# hasp_interface.net
KiCad netlist of a schematic drawn in EAGLE
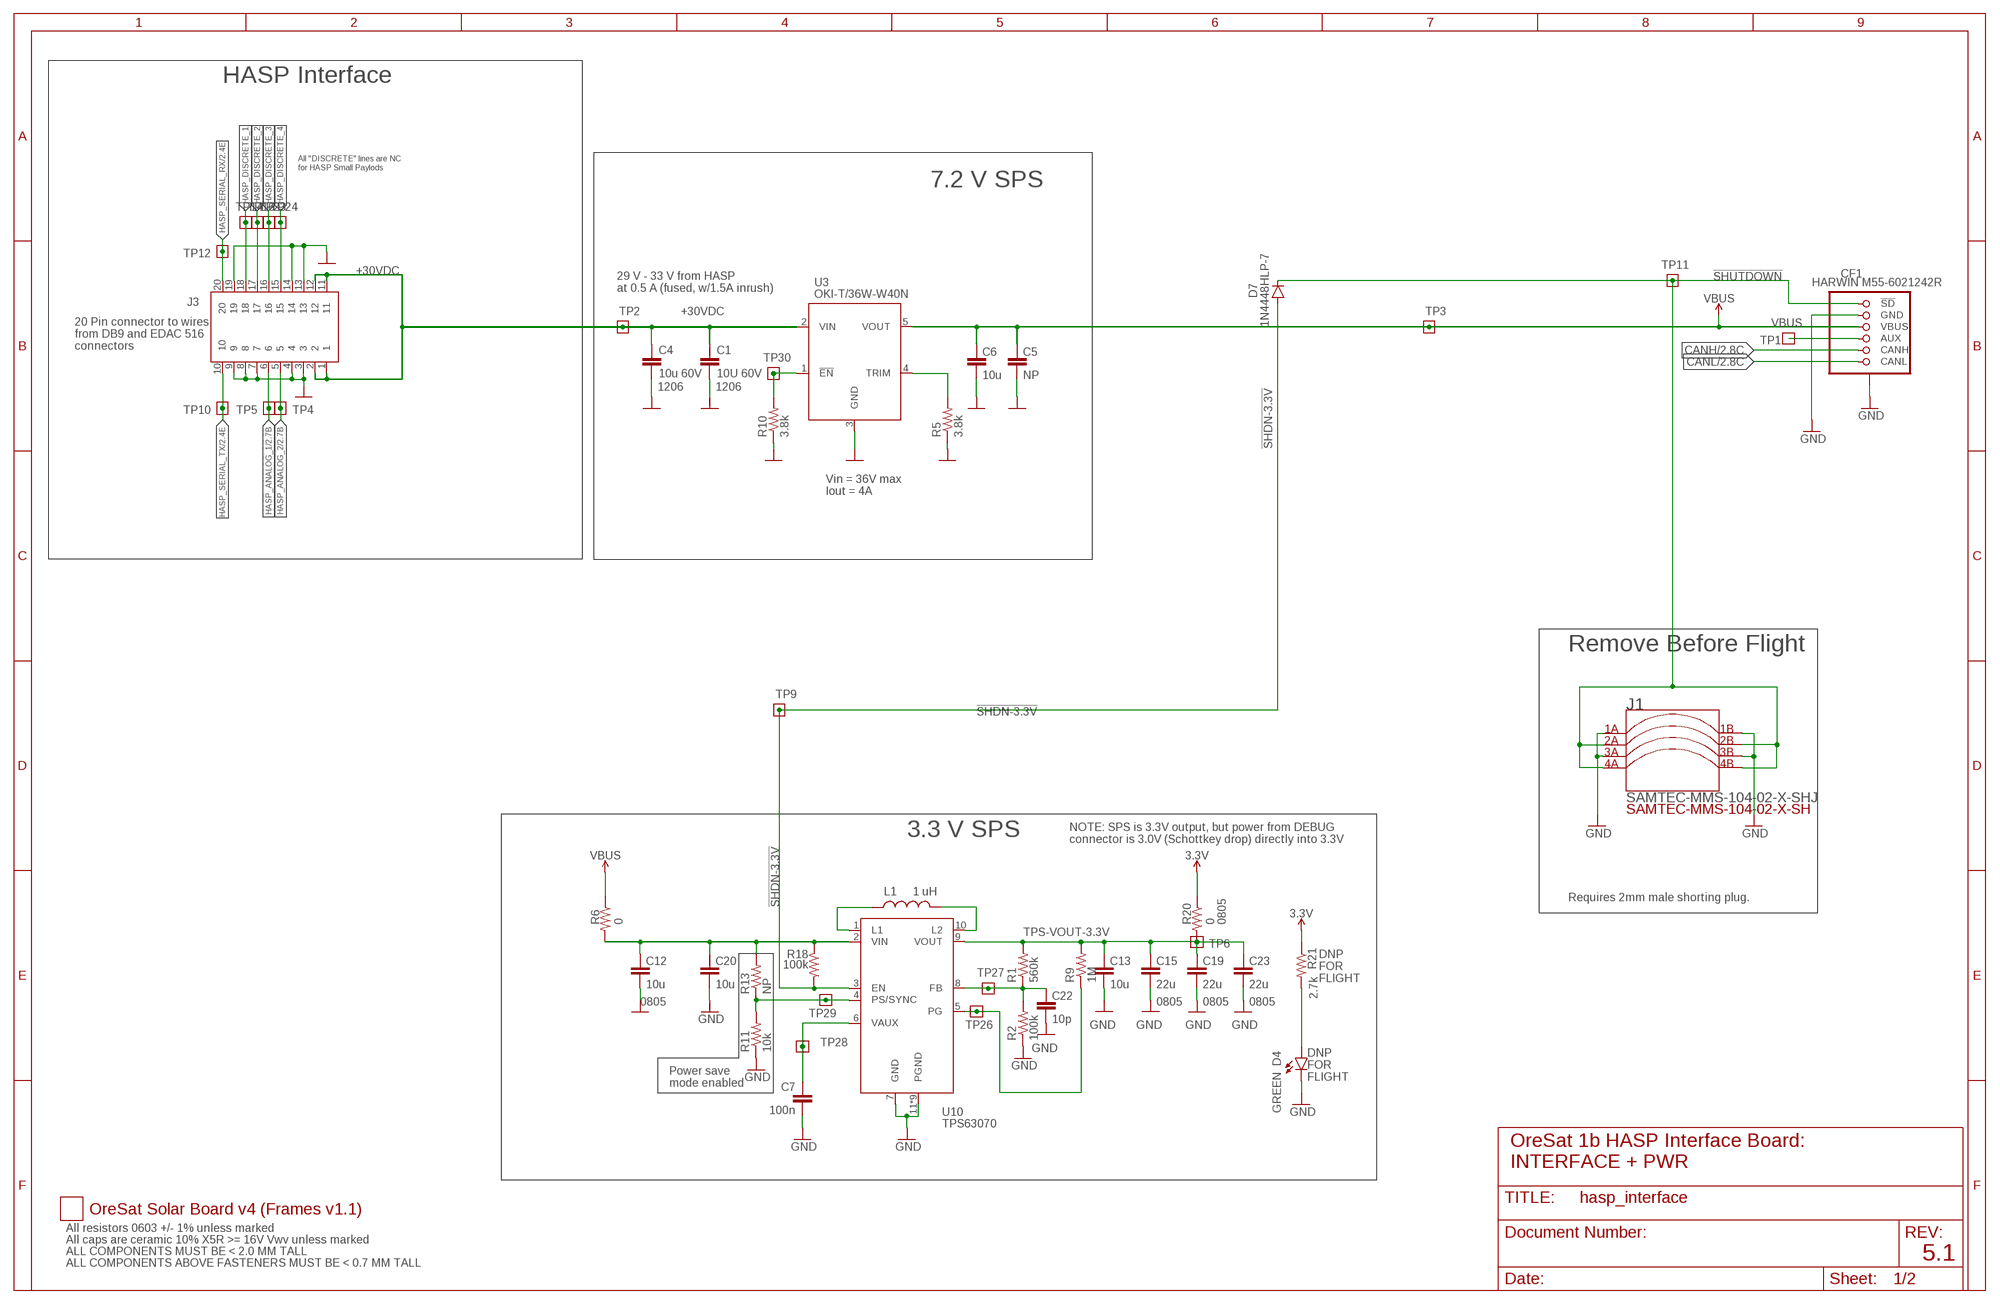
[diagram p0: schematic, sheet 1]
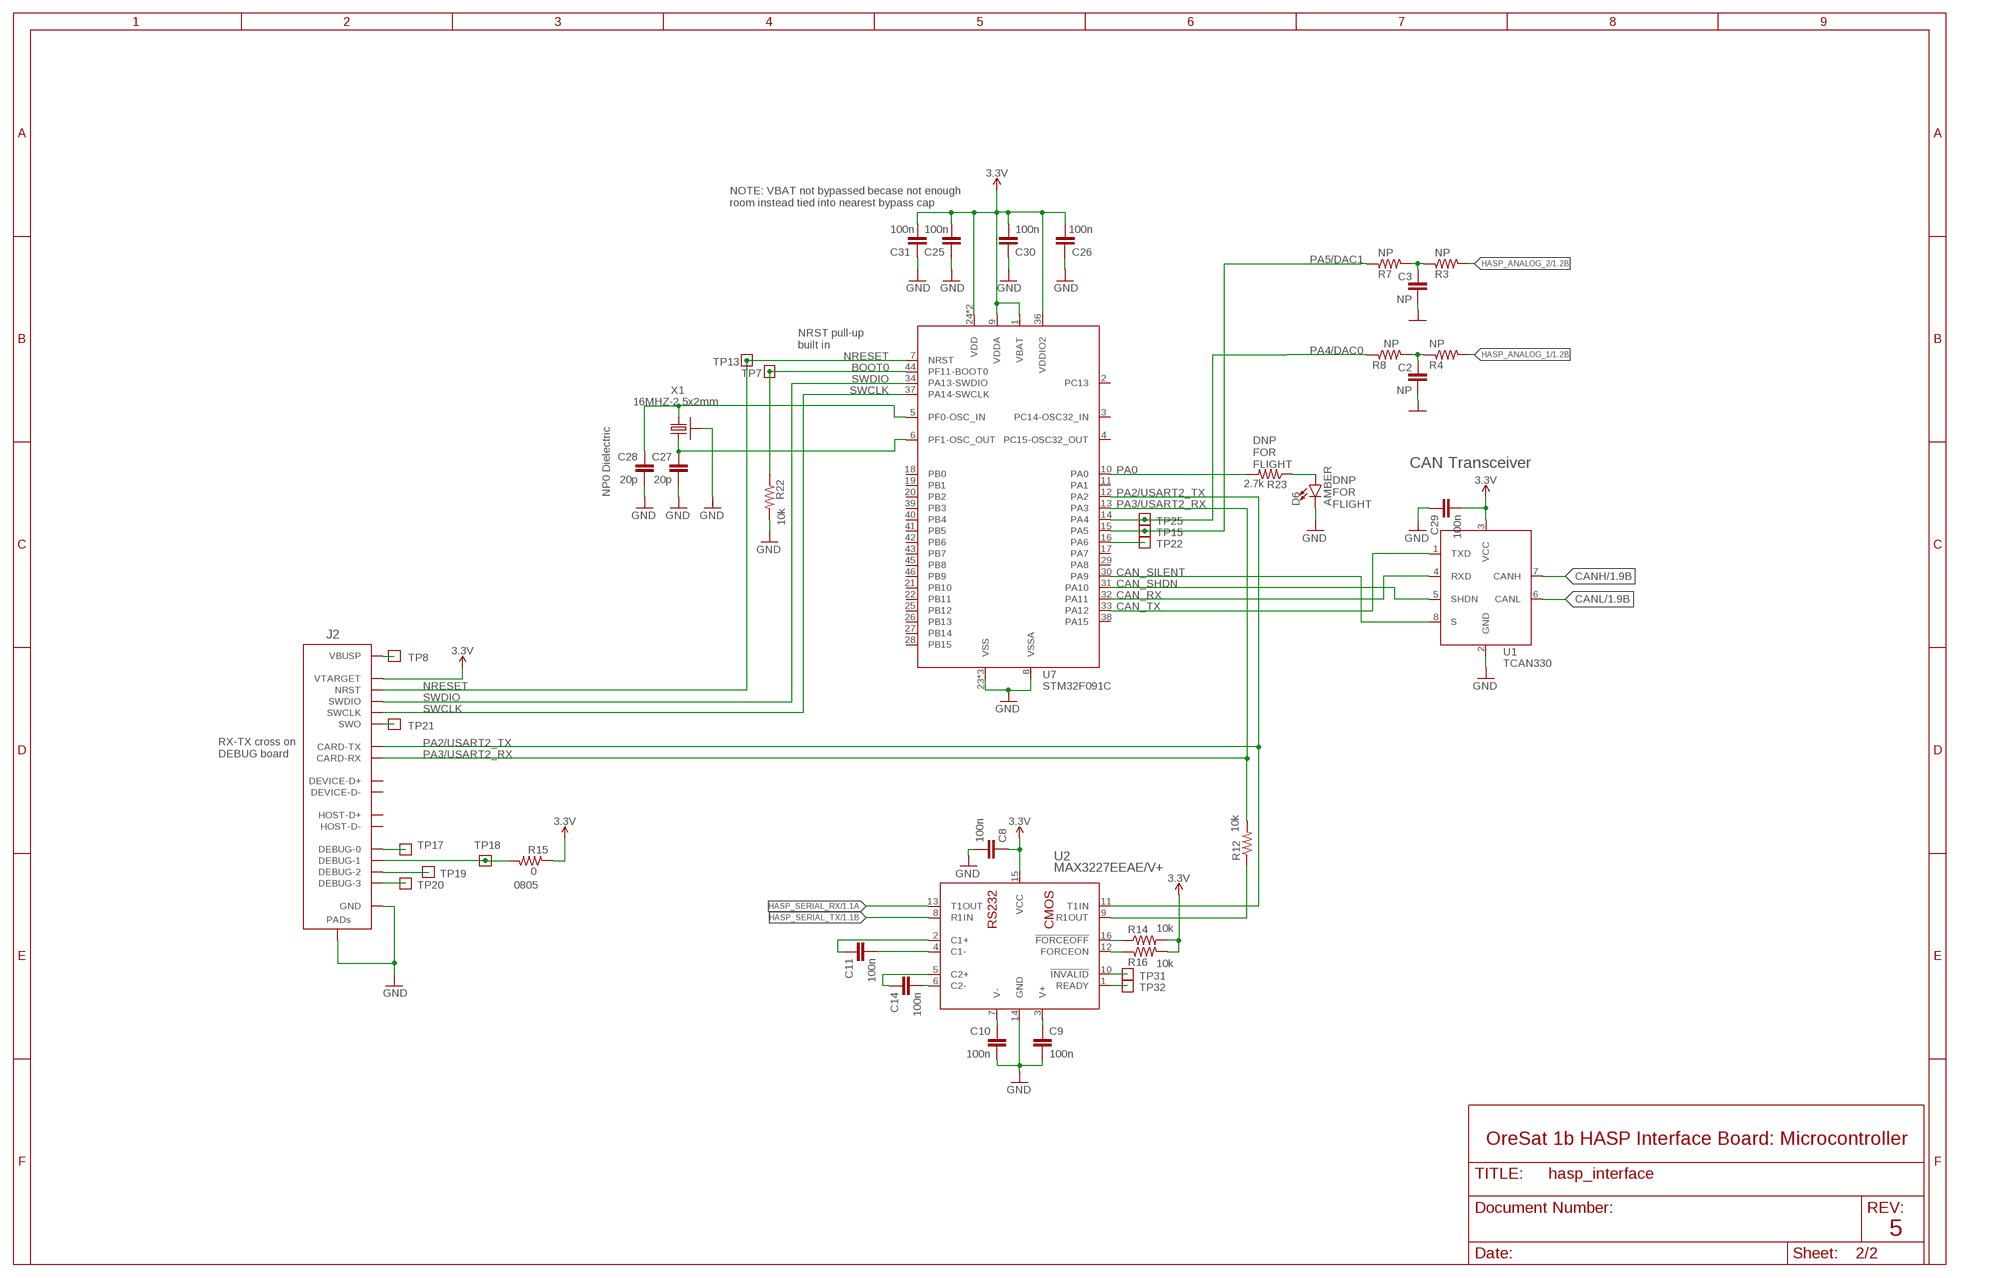
[diagram p1: schematic, sheet 2]

(export (version "E")
  (design (tool "Eeschema 10.0.6"))
  (components
    (comp (ref "C1")
      (value "10U 60V")
      (footprint "eagle-import:1206-C")
      (libsource (lib "eagle-import") (part "C-EU1206-C"))
    )
    (comp (ref "C4")
      (value "10u 60V")
      (footprint "eagle-import:1206-C")
      (libsource (lib "eagle-import") (part "C-EU1206-C"))
    )
    (comp (ref "C5")
      (value "NP")
      (footprint "eagle-import:.0603-C-NOSILK")
      (fields (field (name "MFR") "Murata") (field (name "MPN") "GRT188R61C106KE13D"))
      (libsource (lib "eagle-import") (part "C-EU0603-C-NOSILK"))
    )
    (comp (ref "C6")
      (value "10u")
      (footprint "eagle-import:.0603-C-NOSILK")
      (fields (field (name "MFR") "Murata") (field (name "MPN") "GRT188R61C106KE13D"))
      (libsource (lib "eagle-import") (part "C-EU0603-C-NOSILK"))
    )
    (comp (ref "C7")
      (value "100n")
      (footprint "eagle-import:.0603-C-NOSILK")
      (fields (field (name "MFR") "Kemet") (field (name "MPN") "CL10B104KB85PND"))
      (libsource (lib "eagle-import") (part "C-EU0603-C-NOSILK"))
    )
    (comp (ref "C12")
      (value "10u")
      (footprint "eagle-import:.0805-B-NOSILK")
      (fields (field (name "MFR") "Murata") (field (name "MPN") "GRT21BR61C106KE01L"))
      (libsource (lib "eagle-import") (part "C-EU0805-B-NOSILK"))
    )
    (comp (ref "C13")
      (value "10u")
      (footprint "eagle-import:.0603-C-NOSILK")
      (fields (field (name "MFR") "Murata") (field (name "MPN") "GRT188R61C106KE13D"))
      (libsource (lib "eagle-import") (part "C-EU0603-C-NOSILK"))
    )
    (comp (ref "C15")
      (value "22u")
      (footprint "eagle-import:.0805-B-NOSILK")
      (fields (field (name "MFR") "Samsung") (field (name "MPN") "CL32B226KOJVPNE"))
      (libsource (lib "eagle-import") (part "C-EU0805-B-NOSILK"))
    )
    (comp (ref "C19")
      (value "22u")
      (footprint "eagle-import:.0805-B-NOSILK")
      (fields (field (name "MFR") "Samsung") (field (name "MPN") "CL32B226KOJVPNE"))
      (libsource (lib "eagle-import") (part "C-EU0805-B-NOSILK"))
    )
    (comp (ref "C20")
      (value "10u")
      (footprint "eagle-import:.0603-C-NOSILK")
      (fields (field (name "MFR") "Murata") (field (name "MPN") "GRT188R61C106KE13D"))
      (libsource (lib "eagle-import") (part "C-EU0603-C-NOSILK"))
    )
    (comp (ref "C22")
      (value "10p")
      (footprint "eagle-import:.0603-C-NOSILK")
      (fields (field (name "MFR") "Murata") (field (name "MPN") "GRT188R61C106KE13D"))
      (libsource (lib "eagle-import") (part "C-EU0603-C-NOSILK"))
    )
    (comp (ref "C23")
      (value "22u")
      (footprint "eagle-import:.0805-B-NOSILK")
      (fields (field (name "MFR") "Samsung") (field (name "MPN") "CL32B226KOJVPNE"))
      (libsource (lib "eagle-import") (part "C-EU0805-B-NOSILK"))
    )
    (comp (ref "CF1")
      (value "HARWIN M55-6021242R")
      (footprint "eagle-import:HARWIN-M55-60X1242R")
      (fields (field (name "MFR") "HARWIN") (field (name "MPN") "M55-6021242R"))
      (libsource (lib "eagle-import") (part "SOLAR-BOARD-CONNECTOR"))
    )
    (comp (ref "D4")
      (value "GREEN")
      (footprint "eagle-import:LED-0603")
      (fields (field (name "MFR") "Inolux") (field (name "MPN") "IN-S63AT5A"))
      (libsource (lib "eagle-import") (part "LED-GREEN0603"))
    )
    (comp (ref "D7")
      (value "1N4448HLP-7")
      (footprint "eagle-import:.0402-B-NOSILK-DIODE")
      (fields (field (name "MFR") "Diodes Inc"))
      (libsource (lib "eagle-import") (part "D-0402"))
    )
    (comp (ref "J1")
      (value "SAMTEC-MMS-104-02-X-SHJ")
      (footprint "eagle-import:SAMTEC-MMS-104-02-X-SH")
      (libsource (lib "eagle-import") (part "SAMTEC-MMS-104-02-X-SHJ"))
    )
    (comp (ref "J3")
      (value "MOLEX-43045XXXXRIGHTANGLE")
      (footprint "eagle-import:0430452000")
      (libsource (lib "eagle-import") (part "MOLEX-43045XXXXRIGHTANGLE"))
    )
    (comp (ref "L1")
      (value "1 uH")
      (footprint "eagle-import:IND_1226AS-H-1R0N=P2")
      (fields (field (name "MFR") "TDK") (field (name "MPN") "VLS3010CX-1R5M-1"))
      (libsource (lib "eagle-import") (part "L-MURATA-1226AS-H-1R0N=P2"))
    )
    (comp (ref "PCB1")
      (value "ORESAT-SOLAR-BOARD-V4-SPECTROLABS")
      (footprint "eagle-import:ORESAT-SOLAR-BOARD-V4")
      (libsource (lib "eagle-import") (part "ORESAT-SOLAR-BOARD-V4-SPECTROLABS"))
    )
    (comp (ref "R1")
      (value "560k")
      (footprint "eagle-import:.0603-C-NOSILK")
      (fields (field (name "MFR") "TE") (field (name "MPN") "CRGCQ0603F470K"))
      (libsource (lib "eagle-import") (part "R-US_0603-C-NOSILK"))
    )
    (comp (ref "R2")
      (value "100k")
      (footprint "eagle-import:.0603-C-NOSILK")
      (fields (field (name "MFR") "Susumu") (field (name "MPN") "RR0816P-104-D"))
      (libsource (lib "eagle-import") (part "R-US_0603-C-NOSILK"))
    )
    (comp (ref "R5")
      (value "3.8k")
      (footprint "eagle-import:.0603-C-NOSILK")
      (libsource (lib "eagle-import") (part "R-US_0603-C-NOSILK"))
    )
    (comp (ref "R6")
      (value "0")
      (footprint "eagle-import:.0805-C-NOSILK")
      (fields (field (name "MFR") "Stackpole") (field (name "MPN") "RMCF0805ZT0R00"))
      (libsource (lib "eagle-import") (part "R-US_0805-C-NOSILK"))
    )
    (comp (ref "R9")
      (value "1M")
      (footprint "eagle-import:.0603-C-NOSILK")
      (libsource (lib "eagle-import") (part "R-US_0603-C-NOSILK"))
    )
    (comp (ref "R10")
      (value "3.8k")
      (footprint "eagle-import:.0603-C-NOSILK")
      (libsource (lib "eagle-import") (part "R-US_0603-C-NOSILK"))
    )
    (comp (ref "R11")
      (value "10k")
      (footprint "eagle-import:.0603-C-NOSILK")
      (libsource (lib "eagle-import") (part "R-US_0603-C-NOSILK"))
    )
    (comp (ref "R13")
      (value "NP")
      (footprint "eagle-import:.0603-C-NOSILK")
      (fields (field (name "MFR") "Stackpole") (field (name "MPN") "RNCP0603FTD10K0"))
      (libsource (lib "eagle-import") (part "R-US_0603-C-NOSILK"))
    )
    (comp (ref "R18")
      (value "100k")
      (footprint "eagle-import:.0603-C-NOSILK")
      (fields (field (name "MFR") "Stackpole") (field (name "MPN") "RNCP0603FTD10K0"))
      (libsource (lib "eagle-import") (part "R-US_0603-C-NOSILK"))
    )
    (comp (ref "R20")
      (value "0")
      (footprint "eagle-import:.0805-C-NOSILK")
      (fields (field (name "MFR") "Stackpole") (field (name "MPN") "RMCF0805ZT0R00"))
      (libsource (lib "eagle-import") (part "R-US_0805-C-NOSILK"))
    )
    (comp (ref "R21")
      (value "2.7k")
      (footprint "eagle-import:.0603-C-NOSILK")
      (fields (field (name "MFR") "TE") (field (name "MPN") "CRGCQ0603F2K7"))
      (libsource (lib "eagle-import") (part "R-US_0603-C-NOSILK"))
    )
    (comp (ref "TP1")
      (value "TEST-POINT-LARGE-SQUARE")
      (footprint "eagle-import:1X01")
      (libsource (lib "eagle-import") (part "TEST-POINT-LARGE-SQUARE"))
    )
    (comp (ref "TP2")
      (value "TEST-POINT-LARGE-SQUARE")
      (footprint "eagle-import:1X01")
      (libsource (lib "eagle-import") (part "TEST-POINT-LARGE-SQUARE"))
    )
    (comp (ref "TP3")
      (value "TEST-POINT-LARGE-SQUARE")
      (footprint "eagle-import:1X01")
      (libsource (lib "eagle-import") (part "TEST-POINT-LARGE-SQUARE"))
    )
    (comp (ref "TP4")
      (value "TEST-POINT-LARGE-SQUARE")
      (footprint "eagle-import:1X01")
      (libsource (lib "eagle-import") (part "TEST-POINT-LARGE-SQUARE"))
    )
    (comp (ref "TP5")
      (value "TEST-POINT-LARGE-SQUARE")
      (footprint "eagle-import:1X01")
      (libsource (lib "eagle-import") (part "TEST-POINT-LARGE-SQUARE"))
    )
    (comp (ref "TP6")
      (value "TEST-POINT-LARGE-SQUARE")
      (footprint "eagle-import:1X01")
      (libsource (lib "eagle-import") (part "TEST-POINT-LARGE-SQUARE"))
    )
    (comp (ref "TP9")
      (value "TEST-POINT-LARGE-SQUARE")
      (footprint "eagle-import:1X01")
      (libsource (lib "eagle-import") (part "TEST-POINT-LARGE-SQUARE"))
    )
    (comp (ref "TP10")
      (value "TEST-POINT-LARGE-SQUARE")
      (footprint "eagle-import:1X01")
      (libsource (lib "eagle-import") (part "TEST-POINT-LARGE-SQUARE"))
    )
    (comp (ref "TP11")
      (value "TEST-POINT-LARGE-SQUARE")
      (footprint "eagle-import:1X01")
      (libsource (lib "eagle-import") (part "TEST-POINT-LARGE-SQUARE"))
    )
    (comp (ref "TP12")
      (value "TEST-POINT-LARGE-SQUARE")
      (footprint "eagle-import:1X01")
      (libsource (lib "eagle-import") (part "TEST-POINT-LARGE-SQUARE"))
    )
    (comp (ref "TP14")
      (value "TEST-POINT-LARGE-SQUARE")
      (footprint "eagle-import:1X01")
      (libsource (lib "eagle-import") (part "TEST-POINT-LARGE-SQUARE"))
    )
    (comp (ref "TP16")
      (value "TEST-POINT-LARGE-SQUARE")
      (footprint "eagle-import:1X01")
      (libsource (lib "eagle-import") (part "TEST-POINT-LARGE-SQUARE"))
    )
    (comp (ref "TP23")
      (value "TEST-POINT-LARGE-SQUARE")
      (footprint "eagle-import:1X01")
      (libsource (lib "eagle-import") (part "TEST-POINT-LARGE-SQUARE"))
    )
    (comp (ref "TP24")
      (value "TEST-POINT-LARGE-SQUARE")
      (footprint "eagle-import:1X01")
      (libsource (lib "eagle-import") (part "TEST-POINT-LARGE-SQUARE"))
    )
    (comp (ref "TP26")
      (value "TEST-POINT-LARGE-SQUARE")
      (footprint "eagle-import:1X01")
      (libsource (lib "eagle-import") (part "TEST-POINT-LARGE-SQUARE"))
    )
    (comp (ref "TP27")
      (value "TEST-POINT-LARGE-SQUARE")
      (footprint "eagle-import:1X01")
      (libsource (lib "eagle-import") (part "TEST-POINT-LARGE-SQUARE"))
    )
    (comp (ref "TP28")
      (value "TEST-POINT-LARGE-SQUARE")
      (footprint "eagle-import:1X01")
      (libsource (lib "eagle-import") (part "TEST-POINT-LARGE-SQUARE"))
    )
    (comp (ref "TP29")
      (value "TEST-POINT-LARGE-SQUARE")
      (footprint "eagle-import:1X01")
      (libsource (lib "eagle-import") (part "TEST-POINT-LARGE-SQUARE"))
    )
    (comp (ref "TP30")
      (value "TEST-POINT-LARGE-SQUARE")
      (footprint "eagle-import:1X01")
      (libsource (lib "eagle-import") (part "TEST-POINT-LARGE-SQUARE"))
    )
    (comp (ref "U3")
      (value "OKI-T/36W-W40N")
      (footprint "eagle-import:OKI-T_36W-W40")
      (libsource (lib "eagle-import") (part "OKI-T/36W-W40"))
    )
    (comp (ref "U10")
      (value "TPS63070")
      (footprint "eagle-import:CONV_TPS63060DSCT")
      (fields (field (name "MFR") "Texas Instruments") (field (name "MPN") "TPS63070RNMT"))
      (libsource (lib "eagle-import") (part "U-TI-TPS63060DCT-BUCKBOOST"))
    )
    (comp (ref "C2")
      (value "NP")
      (footprint "eagle-import:.0603-C-NOSILK")
      (fields (field (name "MFR") "Murata") (field (name "MPN") "GRT188R61C106KE13D"))
      (libsource (lib "eagle-import") (part "C-EU0603-C-NOSILK"))
    )
    (comp (ref "C3")
      (value "NP")
      (footprint "eagle-import:.0603-C-NOSILK")
      (fields (field (name "MFR") "Murata") (field (name "MPN") "GRT188R61C106KE13D"))
      (libsource (lib "eagle-import") (part "C-EU0603-C-NOSILK"))
    )
    (comp (ref "C8")
      (value "100n")
      (footprint "eagle-import:.0603-C-NOSILK")
      (fields (field (name "MFR") "Kemet") (field (name "MPN") "CL10B104KB85PND"))
      (libsource (lib "eagle-import") (part "C-EU0603-C-NOSILK"))
    )
    (comp (ref "C9")
      (value "100n")
      (footprint "eagle-import:.0603-C-NOSILK")
      (fields (field (name "MFR") "Kemet") (field (name "MPN") "CL10B104KB85PND"))
      (libsource (lib "eagle-import") (part "C-EU0603-C-NOSILK"))
    )
    (comp (ref "C10")
      (value "100n")
      (footprint "eagle-import:.0603-C-NOSILK")
      (fields (field (name "MFR") "Kemet") (field (name "MPN") "CL10B104KB85PND"))
      (libsource (lib "eagle-import") (part "C-EU0603-C-NOSILK"))
    )
    (comp (ref "C11")
      (value "100n")
      (footprint "eagle-import:.0603-C-NOSILK")
      (fields (field (name "MFR") "Kemet") (field (name "MPN") "CL10B104KB85PND"))
      (libsource (lib "eagle-import") (part "C-EU0603-C-NOSILK"))
    )
    (comp (ref "C14")
      (value "100n")
      (footprint "eagle-import:.0603-C-NOSILK")
      (fields (field (name "MFR") "Kemet") (field (name "MPN") "CL10B104KB85PND"))
      (libsource (lib "eagle-import") (part "C-EU0603-C-NOSILK"))
    )
    (comp (ref "C25")
      (value "100n")
      (footprint "eagle-import:.0603-C-NOSILK")
      (fields (field (name "MFR") "Kemet") (field (name "MPN") "CL10B104KB85PND"))
      (libsource (lib "eagle-import") (part "C-EU0603-C-NOSILK"))
    )
    (comp (ref "C26")
      (value "100n")
      (footprint "eagle-import:.0603-C-NOSILK")
      (fields (field (name "MFR") "Kemet") (field (name "MPN") "CL10B104KB85PND"))
      (libsource (lib "eagle-import") (part "C-EU0603-C-NOSILK"))
    )
    (comp (ref "C27")
      (value "20p")
      (footprint "eagle-import:.0603-C-NOSILK")
      (fields (field (name "MFR") "Murata") (field (name "MPN") "GCM1885C2A200JA16D"))
      (libsource (lib "eagle-import") (part "C-EU0603-C-NOSILK"))
    )
    (comp (ref "C28")
      (value "20p")
      (footprint "eagle-import:.0603-C-NOSILK")
      (fields (field (name "MFR") "Murata") (field (name "MPN") "GCM1885C2A200JA16D"))
      (libsource (lib "eagle-import") (part "C-EU0603-C-NOSILK"))
    )
    (comp (ref "C29")
      (value "100n")
      (footprint "eagle-import:.0603-C-NOSILK")
      (fields (field (name "MFR") "Kemet") (field (name "MPN") "CL10B104KB85PND"))
      (libsource (lib "eagle-import") (part "C-EU0603-C-NOSILK"))
    )
    (comp (ref "C30")
      (value "100n")
      (footprint "eagle-import:.0603-C-NOSILK")
      (fields (field (name "MFR") "Kemet") (field (name "MPN") "CL10B104KB85PND"))
      (libsource (lib "eagle-import") (part "C-EU0603-C-NOSILK"))
    )
    (comp (ref "C31")
      (value "100n")
      (footprint "eagle-import:.0603-C-NOSILK")
      (fields (field (name "MFR") "Kemet") (field (name "MPN") "CL10B104KB85PND"))
      (libsource (lib "eagle-import") (part "C-EU0603-C-NOSILK"))
    )
    (comp (ref "D6")
      (value "AMBER")
      (footprint "eagle-import:LED-0603")
      (fields (field (name "MFR") "Inolux") (field (name "MPN") "IN-S63AT5A"))
      (libsource (lib "eagle-import") (part "LED-GREEN0603"))
    )
    (comp (ref "J2")
      (value "ORESAT-DEBUG-CONNECTOR-ALL")
      (footprint "eagle-import:TE_2-1734592-0")
      (fields
        (field (name "MPN") "2-1734592-0")
        (field (name "DPN") "732-11341-1-ND")
        (field (name "MFR") "Wurth")
        (field (name "MPN_1") "687120183622  ")
      )
      (libsource (lib "eagle-import") (part "ORESAT-DEBUG-CONNECTOR-ALL"))
    )
    (comp (ref "R3")
      (value "NP")
      (footprint "eagle-import:.0603-C-NOSILK")
      (libsource (lib "eagle-import") (part "R-US_0603-C-NOSILK"))
    )
    (comp (ref "R4")
      (value "NP")
      (footprint "eagle-import:.0603-C-NOSILK")
      (libsource (lib "eagle-import") (part "R-US_0603-C-NOSILK"))
    )
    (comp (ref "R7")
      (value "NP")
      (footprint "eagle-import:.0603-C-NOSILK")
      (libsource (lib "eagle-import") (part "R-US_0603-C-NOSILK"))
    )
    (comp (ref "R8")
      (value "NP")
      (footprint "eagle-import:.0603-C-NOSILK")
      (libsource (lib "eagle-import") (part "R-US_0603-C-NOSILK"))
    )
    (comp (ref "R12")
      (value "10k")
      (footprint "eagle-import:.0603-C-NOSILK")
      (fields (field (name "MFR") "TE") (field (name "MPN") "CRGCQ0603F2K7"))
      (libsource (lib "eagle-import") (part "R-US_0603-C-NOSILK"))
    )
    (comp (ref "R14")
      (value "10k")
      (footprint "eagle-import:.0603-C-NOSILK")
      (fields (field (name "MFR") "TE") (field (name "MPN") "CRGCQ0603F2K7"))
      (libsource (lib "eagle-import") (part "R-US_0603-C-NOSILK"))
    )
    (comp (ref "R15")
      (value "0")
      (footprint "eagle-import:.0805-C-NOSILK")
      (fields (field (name "MFR") "Stackpole") (field (name "MPN") "RMCF0805ZT0R00"))
      (libsource (lib "eagle-import") (part "R-US_0805-C-NOSILK"))
    )
    (comp (ref "R16")
      (value "10k")
      (footprint "eagle-import:.0603-C-NOSILK")
      (fields (field (name "MFR") "TE") (field (name "MPN") "CRGCQ0603F2K7"))
      (libsource (lib "eagle-import") (part "R-US_0603-C-NOSILK"))
    )
    (comp (ref "R22")
      (value "10k")
      (footprint "eagle-import:.0603-C-NOSILK")
      (fields (field (name "MFR") "TE") (field (name "MPN") "CRGCQ0603F2K7"))
      (libsource (lib "eagle-import") (part "R-US_0603-C-NOSILK"))
    )
    (comp (ref "R23")
      (value "2.7k")
      (footprint "eagle-import:.0603-C-NOSILK")
      (fields (field (name "MFR") "TE") (field (name "MPN") "CRGCQ0603F2K7"))
      (libsource (lib "eagle-import") (part "R-US_0603-C-NOSILK"))
    )
    (comp (ref "TP7")
      (value "TEST-POINT-LARGE-SQUARE")
      (footprint "eagle-import:1X01")
      (libsource (lib "eagle-import") (part "TEST-POINT-LARGE-SQUARE"))
    )
    (comp (ref "TP8")
      (value "TEST-POINT-LARGE-SQUARE")
      (footprint "eagle-import:1X01")
      (libsource (lib "eagle-import") (part "TEST-POINT-LARGE-SQUARE"))
    )
    (comp (ref "TP13")
      (value "TEST-POINT-LARGE-SQUARE")
      (footprint "eagle-import:1X01")
      (libsource (lib "eagle-import") (part "TEST-POINT-LARGE-SQUARE"))
    )
    (comp (ref "TP15")
      (value "TEST-POINT-LARGE-SQUARE")
      (footprint "eagle-import:1X01")
      (libsource (lib "eagle-import") (part "TEST-POINT-LARGE-SQUARE"))
    )
    (comp (ref "TP17")
      (value "TEST-POINT-LARGE-SQUARE")
      (footprint "eagle-import:1X01")
      (libsource (lib "eagle-import") (part "TEST-POINT-LARGE-SQUARE"))
    )
    (comp (ref "TP18")
      (value "TEST-POINT-LARGE-SQUARE")
      (footprint "eagle-import:1X01")
      (libsource (lib "eagle-import") (part "TEST-POINT-LARGE-SQUARE"))
    )
    (comp (ref "TP19")
      (value "TEST-POINT-LARGE-SQUARE")
      (footprint "eagle-import:1X01")
      (libsource (lib "eagle-import") (part "TEST-POINT-LARGE-SQUARE"))
    )
    (comp (ref "TP20")
      (value "TEST-POINT-LARGE-SQUARE")
      (footprint "eagle-import:1X01")
      (libsource (lib "eagle-import") (part "TEST-POINT-LARGE-SQUARE"))
    )
    (comp (ref "TP21")
      (value "TEST-POINT-LARGE-SQUARE")
      (footprint "eagle-import:1X01")
      (libsource (lib "eagle-import") (part "TEST-POINT-LARGE-SQUARE"))
    )
    (comp (ref "TP22")
      (value "TEST-POINT-LARGE-SQUARE")
      (footprint "eagle-import:1X01")
      (libsource (lib "eagle-import") (part "TEST-POINT-LARGE-SQUARE"))
    )
    (comp (ref "TP25")
      (value "TEST-POINT-LARGE-SQUARE")
      (footprint "eagle-import:1X01")
      (libsource (lib "eagle-import") (part "TEST-POINT-LARGE-SQUARE"))
    )
    (comp (ref "TP31")
      (value "TEST-POINT-LARGE-SQUARE")
      (footprint "eagle-import:1X01")
      (libsource (lib "eagle-import") (part "TEST-POINT-LARGE-SQUARE"))
    )
    (comp (ref "TP32")
      (value "TEST-POINT-LARGE-SQUARE")
      (footprint "eagle-import:1X01")
      (libsource (lib "eagle-import") (part "TEST-POINT-LARGE-SQUARE"))
    )
    (comp (ref "U1")
      (value "TCAN330")
      (footprint "eagle-import:SOT23-8_TI-DCN")
      (fields (field (name "MFR") "Texas Instruments") (field (name "MPN") "TCAN330GDCNT"))
      (libsource (lib "eagle-import") (part "TCAN330"))
    )
    (comp (ref "U2")
      (value "MAX3227EEAE/V+")
      (footprint "eagle-import:21-0056_A16+2_MXM")
      (libsource (lib "eagle-import") (part "MAX3227EEAE/V+"))
    )
    (comp (ref "U7")
      (value "STM32F091C")
      (footprint "eagle-import:STM32F091C")
      (fields (field (name "MFR") "STMicroelectronics") (field (name "MPN") "STM32F091CCT6TR"))
      (libsource (lib "eagle-import") (part "STM32F091C"))
    )
    (comp (ref "X1")
      (value "16MHZ-2.5x2mm")
      (footprint "eagle-import:CRYSTAL_2.5X2")
      (fields (field (name "MFR") "ECS Inc.") (field (name "MPN") "ECS-160-10-36Q-ES-TR"))
      (libsource (lib "eagle-import") (part "CRYSTAL-WITH-GND"))
    )
  )
  (nets
    (net (code "1") (name "+30VDC") (class "Default")
      (node (ref "C1") (pin "1") (pinfunction "1_1") (pintype "passive"))
      (node (ref "C4") (pin "1") (pinfunction "1_1") (pintype "passive"))
      (node (ref "J3") (pin "1") (pinfunction "1_1") (pintype "bidirectional"))
      (node (ref "J3") (pin "11") (pinfunction "11_11") (pintype "bidirectional"))
      (node (ref "J3") (pin "12") (pinfunction "12_12") (pintype "bidirectional"))
      (node (ref "J3") (pin "2") (pinfunction "2_2") (pintype "bidirectional"))
      (node (ref "TP2") (pin "1") (pinfunction "1_1") (pintype "passive"))
      (node (ref "U3") (pin "2") (pinfunction "VIN_2") (pintype "power_in"))
    )
    (net (code "2") (name "3.3V") (class "Default")
      (node (ref "C25") (pin "2") (pinfunction "2_2") (pintype "passive"))
      (node (ref "C26") (pin "2") (pinfunction "2_2") (pintype "passive"))
      (node (ref "C29") (pin "2") (pinfunction "2_2") (pintype "passive"))
      (node (ref "C30") (pin "2") (pinfunction "2_2") (pintype "passive"))
      (node (ref "C31") (pin "2") (pinfunction "2_2") (pintype "passive"))
      (node (ref "C8") (pin "1") (pinfunction "1_1") (pintype "passive"))
      (node (ref "J2") (pin "11") (pinfunction "VTARGET_11") (pintype "passive"))
      (node (ref "R14") (pin "2") (pinfunction "2_2") (pintype "passive"))
      (node (ref "R15") (pin "1") (pinfunction "1_1") (pintype "passive"))
      (node (ref "R16") (pin "2") (pinfunction "2_2") (pintype "passive"))
      (node (ref "R20") (pin "1") (pinfunction "1_1") (pintype "passive"))
      (node (ref "R21") (pin "1") (pinfunction "1_1") (pintype "passive"))
      (node (ref "U1") (pin "3") (pinfunction "VCC_3") (pintype "power_in"))
      (node (ref "U2") (pin "15") (pinfunction "VCC_15") (pintype "power_in"))
      (node (ref "U7") (pin "1") (pinfunction "VBAT_1") (pintype "power_in"))
      (node (ref "U7") (pin "24") (pinfunction "VDD_24") (pintype "power_in"))
      (node (ref "U7") (pin "36") (pinfunction "VDDIO2_36") (pintype "power_in"))
      (node (ref "U7") (pin "48") (pinfunction "VDD_48") (pintype "power_in"))
      (node (ref "U7") (pin "9") (pinfunction "VDDA_9") (pintype "power_in"))
    )
    (net (code "3") (name "BOOT0") (class "Default")
      (node (ref "R22") (pin "1") (pinfunction "1_1") (pintype "passive"))
      (node (ref "TP7") (pin "1") (pinfunction "1_1") (pintype "passive"))
      (node (ref "U7") (pin "44") (pinfunction "PF11-BOOT0_44") (pintype "bidirectional"))
    )
    (net (code "4") (name "CANH") (class "Default")
      (node (ref "CF1") (pin "10") (pinfunction "CANH_10") (pintype "passive"))
      (node (ref "CF1") (pin "9") (pinfunction "CANH_9") (pintype "passive"))
      (node (ref "U1") (pin "7") (pinfunction "CANH_7") (pintype "bidirectional"))
    )
    (net (code "5") (name "CANL") (class "Default")
      (node (ref "CF1") (pin "11") (pinfunction "CANL_11") (pintype "passive"))
      (node (ref "CF1") (pin "12") (pinfunction "CANL_12") (pintype "passive"))
      (node (ref "U1") (pin "6") (pinfunction "CANL_6") (pintype "bidirectional"))
    )
    (net (code "6") (name "CAN_RX") (class "Default")
      (node (ref "U1") (pin "4") (pinfunction "RXD_4") (pintype "output"))
      (node (ref "U7") (pin "32") (pinfunction "PA11_32") (pintype "bidirectional"))
    )
    (net (code "7") (name "CAN_SHDN") (class "Default")
      (node (ref "U1") (pin "5") (pinfunction "SHDN_5") (pintype "input"))
      (node (ref "U7") (pin "31") (pinfunction "PA10_31") (pintype "bidirectional"))
    )
    (net (code "8") (name "CAN_SILENT") (class "Default")
      (node (ref "U1") (pin "8") (pinfunction "S_8") (pintype "input"))
      (node (ref "U7") (pin "30") (pinfunction "PA9_30") (pintype "bidirectional"))
    )
    (net (code "9") (name "CAN_TX") (class "Default")
      (node (ref "U1") (pin "1") (pinfunction "TXD_1") (pintype "input"))
      (node (ref "U7") (pin "33") (pinfunction "PA12_33") (pintype "bidirectional"))
    )
    (net (code "10") (name "GND") (class "Default")
      (node (ref "C1") (pin "2") (pinfunction "2_2") (pintype "passive"))
      (node (ref "C10") (pin "2") (pinfunction "2_2") (pintype "passive"))
      (node (ref "C12") (pin "2") (pinfunction "2_2") (pintype "passive"))
      (node (ref "C13") (pin "2") (pinfunction "2_2") (pintype "passive"))
      (node (ref "C15") (pin "2") (pinfunction "2_2") (pintype "passive"))
      (node (ref "C19") (pin "2") (pinfunction "2_2") (pintype "passive"))
      (node (ref "C2") (pin "2") (pinfunction "2_2") (pintype "passive"))
      (node (ref "C20") (pin "2") (pinfunction "2_2") (pintype "passive"))
      (node (ref "C22") (pin "2") (pinfunction "2_2") (pintype "passive"))
      (node (ref "C23") (pin "2") (pinfunction "2_2") (pintype "passive"))
      (node (ref "C25") (pin "1") (pinfunction "1_1") (pintype "passive"))
      (node (ref "C26") (pin "1") (pinfunction "1_1") (pintype "passive"))
      (node (ref "C27") (pin "2") (pinfunction "2_2") (pintype "passive"))
      (node (ref "C28") (pin "2") (pinfunction "2_2") (pintype "passive"))
      (node (ref "C29") (pin "1") (pinfunction "1_1") (pintype "passive"))
      (node (ref "C3") (pin "2") (pinfunction "2_2") (pintype "passive"))
      (node (ref "C30") (pin "1") (pinfunction "1_1") (pintype "passive"))
      (node (ref "C31") (pin "1") (pinfunction "1_1") (pintype "passive"))
      (node (ref "C4") (pin "2") (pinfunction "2_2") (pintype "passive"))
      (node (ref "C5") (pin "2") (pinfunction "2_2") (pintype "passive"))
      (node (ref "C6") (pin "2") (pinfunction "2_2") (pintype "passive"))
      (node (ref "C7") (pin "2") (pinfunction "2_2") (pintype "passive"))
      (node (ref "C8") (pin "2") (pinfunction "2_2") (pintype "passive"))
      (node (ref "C9") (pin "2") (pinfunction "2_2") (pintype "passive"))
      (node (ref "CF1") (pin "3") (pinfunction "GND_3") (pintype "passive"))
      (node (ref "CF1") (pin "4") (pinfunction "GND_4") (pintype "passive"))
      (node (ref "CF1") (pin "P$1") (pinfunction "SHIELD_P$1") (pintype "passive"))
      (node (ref "CF1") (pin "P$2") (pinfunction "SHIELD_P$2") (pintype "passive"))
      (node (ref "CF1") (pin "P$3") (pinfunction "SHIELD_P$3") (pintype "passive"))
      (node (ref "CF1") (pin "P$4") (pinfunction "SHIELD_P$4") (pintype "passive"))
      (node (ref "D4") (pin "C") (pinfunction "C_C") (pintype "passive"))
      (node (ref "D6") (pin "C") (pinfunction "C_C") (pintype "passive"))
      (node (ref "J1") (pin "1A") (pinfunction "1A_1A") (pintype "passive"))
      (node (ref "J1") (pin "1B") (pinfunction "1B_1B") (pintype "passive"))
      (node (ref "J1") (pin "3A") (pinfunction "3A_3A") (pintype "passive"))
      (node (ref "J1") (pin "3B") (pinfunction "3B_3B") (pintype "passive"))
      (node (ref "J2") (pin "3") (pinfunction "GND_3") (pintype "passive"))
      (node (ref "J2") (pin "6") (pinfunction "GND_6") (pintype "passive"))
      (node (ref "J2") (pin "9") (pinfunction "GND_9") (pintype "passive"))
      (node (ref "J2") (pin "PAD1") (pinfunction "PAD_PAD1") (pintype "bidirectional"))
      (node (ref "J2") (pin "PAD2") (pinfunction "PAD_PAD2") (pintype "bidirectional"))
      (node (ref "J3") (pin "13") (pinfunction "13_13") (pintype "bidirectional"))
      (node (ref "J3") (pin "14") (pinfunction "14_14") (pintype "bidirectional"))
      (node (ref "J3") (pin "19") (pinfunction "19_19") (pintype "bidirectional"))
      (node (ref "J3") (pin "3") (pinfunction "3_3") (pintype "bidirectional"))
      (node (ref "J3") (pin "4") (pinfunction "4_4") (pintype "bidirectional"))
      (node (ref "J3") (pin "7") (pinfunction "7_7") (pintype "bidirectional"))
      (node (ref "J3") (pin "8") (pinfunction "8_8") (pintype "bidirectional"))
      (node (ref "J3") (pin "9") (pinfunction "9_9") (pintype "bidirectional"))
      (node (ref "R10") (pin "1") (pinfunction "1_1") (pintype "passive"))
      (node (ref "R11") (pin "1") (pinfunction "1_1") (pintype "passive"))
      (node (ref "R2") (pin "1") (pinfunction "1_1") (pintype "passive"))
      (node (ref "R22") (pin "2") (pinfunction "2_2") (pintype "passive"))
      (node (ref "R5") (pin "1") (pinfunction "1_1") (pintype "passive"))
      (node (ref "U1") (pin "2") (pinfunction "GND_2") (pintype "power_in"))
      (node (ref "U10") (pin "11") (pinfunction "PGND_11") (pintype "power_in"))
      (node (ref "U10") (pin "12") (pinfunction "PGND_12") (pintype "power_in"))
      (node (ref "U10") (pin "13") (pinfunction "PGND_13") (pintype "power_in"))
      (node (ref "U10") (pin "14") (pinfunction "PGND_14") (pintype "power_in"))
      (node (ref "U10") (pin "15") (pinfunction "PGND_15") (pintype "power_in"))
      (node (ref "U10") (pin "16") (pinfunction "PGND_16") (pintype "power_in"))
      (node (ref "U10") (pin "17") (pinfunction "PGND_17") (pintype "power_in"))
      (node (ref "U10") (pin "18") (pinfunction "PGND_18") (pintype "power_in"))
      (node (ref "U10") (pin "19") (pinfunction "PGND_19") (pintype "power_in"))
      (node (ref "U10") (pin "7") (pinfunction "GND_7") (pintype "power_in"))
      (node (ref "U2") (pin "14") (pinfunction "GND_14") (pintype "power_in"))
      (node (ref "U3") (pin "3") (pinfunction "GND_3") (pintype "power_in"))
      (node (ref "U7") (pin "23") (pinfunction "VSS_23") (pintype "power_in"))
      (node (ref "U7") (pin "35") (pinfunction "VSS_35") (pintype "power_in"))
      (node (ref "U7") (pin "47") (pinfunction "VSS_47") (pintype "power_in"))
      (node (ref "U7") (pin "8") (pinfunction "VSSA_8") (pintype "power_in"))
      (node (ref "X1") (pin "2") (pinfunction "SHIELD_2") (pintype "power_in"))
      (node (ref "X1") (pin "4") (pinfunction "SHIELD_4") (pintype "power_in"))
    )
    (net (code "11") (name "HASP_ANALOG_1") (class "Default")
      (node (ref "J3") (pin "6") (pinfunction "6_6") (pintype "bidirectional"))
      (node (ref "R4") (pin "2") (pinfunction "2_2") (pintype "passive"))
      (node (ref "TP5") (pin "1") (pinfunction "1_1") (pintype "passive"))
    )
    (net (code "12") (name "HASP_ANALOG_2") (class "Default")
      (node (ref "J3") (pin "5") (pinfunction "5_5") (pintype "bidirectional"))
      (node (ref "R3") (pin "2") (pinfunction "2_2") (pintype "passive"))
      (node (ref "TP4") (pin "1") (pinfunction "1_1") (pintype "passive"))
    )
    (net (code "13") (name "HASP_DISCRETE_1") (class "Default")
      (node (ref "J3") (pin "18") (pinfunction "18_18") (pintype "bidirectional"))
      (node (ref "TP14") (pin "1") (pinfunction "1_1") (pintype "passive"))
    )
    (net (code "14") (name "HASP_DISCRETE_2") (class "Default")
      (node (ref "J3") (pin "17") (pinfunction "17_17") (pintype "bidirectional"))
      (node (ref "TP16") (pin "1") (pinfunction "1_1") (pintype "passive"))
    )
    (net (code "15") (name "HASP_DISCRETE_3") (class "Default")
      (node (ref "J3") (pin "16") (pinfunction "16_16") (pintype "bidirectional"))
      (node (ref "TP23") (pin "1") (pinfunction "1_1") (pintype "passive"))
    )
    (net (code "16") (name "HASP_DISCRETE_4") (class "Default")
      (node (ref "J3") (pin "15") (pinfunction "15_15") (pintype "bidirectional"))
      (node (ref "TP24") (pin "1") (pinfunction "1_1") (pintype "passive"))
    )
    (net (code "17") (name "HASP_SERIAL_RX") (class "Default")
      (node (ref "J3") (pin "20") (pinfunction "20_20") (pintype "bidirectional"))
      (node (ref "TP12") (pin "1") (pinfunction "1_1") (pintype "passive"))
      (node (ref "U2") (pin "13") (pinfunction "T1OUT_13") (pintype "output"))
    )
    (net (code "18") (name "HASP_SERIAL_TX") (class "Default")
      (node (ref "J3") (pin "10") (pinfunction "10_10") (pintype "bidirectional"))
      (node (ref "TP10") (pin "1") (pinfunction "1_1") (pintype "passive"))
      (node (ref "U2") (pin "8") (pinfunction "R1IN_8") (pintype "input"))
    )
    (net (code "19") (name "NRESET") (class "Default")
      (node (ref "J2") (pin "10") (pinfunction "NRST_10") (pintype "passive"))
      (node (ref "TP13") (pin "1") (pinfunction "1_1") (pintype "passive"))
      (node (ref "U7") (pin "7") (pinfunction "NRST_7") (pintype "bidirectional"))
    )
    (net (code "20") (name "Net-(C2-Pad1)") (class "Default")
      (node (ref "C2") (pin "1") (pinfunction "1_1") (pintype "passive"))
      (node (ref "R4") (pin "1") (pinfunction "1_1") (pintype "passive"))
      (node (ref "R8") (pin "2") (pinfunction "2_2") (pintype "passive"))
    )
    (net (code "21") (name "Net-(C3-Pad1)") (class "Default")
      (node (ref "C3") (pin "1") (pinfunction "1_1") (pintype "passive"))
      (node (ref "R3") (pin "1") (pinfunction "1_1") (pintype "passive"))
      (node (ref "R7") (pin "2") (pinfunction "2_2") (pintype "passive"))
    )
    (net (code "22") (name "Net-(CF1-AUX-Pad7)") (class "Default")
      (node (ref "CF1") (pin "7") (pinfunction "AUX_7") (pintype "passive"))
      (node (ref "CF1") (pin "8") (pinfunction "AUX_8") (pintype "passive"))
      (node (ref "TP1") (pin "1") (pinfunction "1_1") (pintype "passive"))
    )
    (net (code "23") (name "Net-(D4-PadA)") (class "Default")
      (node (ref "D4") (pin "A") (pinfunction "A_A") (pintype "passive"))
      (node (ref "R21") (pin "2") (pinfunction "2_2") (pintype "passive"))
    )
    (net (code "24") (name "Net-(D6-PadA)") (class "Default")
      (node (ref "D6") (pin "A") (pinfunction "A_A") (pintype "passive"))
      (node (ref "R23") (pin "1") (pinfunction "1_1") (pintype "passive"))
    )
    (net (code "25") (name "Net-(J2-DEBUG-0)") (class "Default")
      (node (ref "J2") (pin "17") (pinfunction "DEBUG-0_17") (pintype "passive"))
      (node (ref "TP17") (pin "1") (pinfunction "1_1") (pintype "passive"))
    )
    (net (code "26") (name "Net-(J2-DEBUG-1)") (class "Default")
      (node (ref "J2") (pin "18") (pinfunction "DEBUG-1_18") (pintype "passive"))
      (node (ref "R15") (pin "2") (pinfunction "2_2") (pintype "passive"))
      (node (ref "TP18") (pin "1") (pinfunction "1_1") (pintype "passive"))
    )
    (net (code "27") (name "Net-(J2-DEBUG-2)") (class "Default")
      (node (ref "J2") (pin "19") (pinfunction "DEBUG-2_19") (pintype "passive"))
      (node (ref "TP19") (pin "1") (pinfunction "1_1") (pintype "passive"))
    )
    (net (code "28") (name "Net-(J2-DEBUG-3)") (class "Default")
      (node (ref "J2") (pin "20") (pinfunction "DEBUG-3_20") (pintype "passive"))
      (node (ref "TP20") (pin "1") (pinfunction "1_1") (pintype "passive"))
    )
    (net (code "29") (name "Net-(J2-SWO)") (class "Default")
      (node (ref "J2") (pin "16") (pinfunction "SWO_16") (pintype "passive"))
      (node (ref "TP21") (pin "1") (pinfunction "1_1") (pintype "passive"))
    )
    (net (code "30") (name "Net-(J2-VBUSP-Pad1)") (class "Default")
      (node (ref "J2") (pin "1") (pinfunction "VBUSP_1") (pintype "passive"))
      (node (ref "J2") (pin "2") (pinfunction "VBUSP_2") (pintype "passive"))
      (node (ref "TP8") (pin "1") (pinfunction "1_1") (pintype "passive"))
    )
    (net (code "31") (name "Net-(U2-C1+)") (class "Default")
      (node (ref "C11") (pin "1") (pinfunction "1_1") (pintype "passive"))
      (node (ref "U2") (pin "2") (pinfunction "C1+_2") (pintype "passive"))
    )
    (net (code "32") (name "Net-(U2-C1-)") (class "Default")
      (node (ref "C11") (pin "2") (pinfunction "2_2") (pintype "passive"))
      (node (ref "U2") (pin "4") (pinfunction "C1-_4") (pintype "passive"))
    )
    (net (code "33") (name "Net-(U2-C2+)") (class "Default")
      (node (ref "C14") (pin "1") (pinfunction "1_1") (pintype "passive"))
      (node (ref "U2") (pin "5") (pinfunction "C2+_5") (pintype "passive"))
    )
    (net (code "34") (name "Net-(U2-C2-)") (class "Default")
      (node (ref "C14") (pin "2") (pinfunction "2_2") (pintype "passive"))
      (node (ref "U2") (pin "6") (pinfunction "C2-_6") (pintype "passive"))
    )
    (net (code "35") (name "Net-(U2-FORCEON)") (class "Default")
      (node (ref "R16") (pin "1") (pinfunction "1_1") (pintype "passive"))
      (node (ref "U2") (pin "12") (pinfunction "FORCEON_12") (pintype "input"))
    )
    (net (code "36") (name "Net-(U2-R1OUT)") (class "Default")
      (node (ref "R12") (pin "1") (pinfunction "1_1") (pintype "passive"))
      (node (ref "U2") (pin "9") (pinfunction "R1OUT_9") (pintype "output"))
    )
    (net (code "37") (name "Net-(U2-READY)") (class "Default")
      (node (ref "TP32") (pin "1") (pinfunction "1_1") (pintype "passive"))
      (node (ref "U2") (pin "1") (pinfunction "READY_1") (pintype "output"))
    )
    (net (code "38") (name "Net-(U2-V+)") (class "Default")
      (node (ref "C9") (pin "1") (pinfunction "1_1") (pintype "passive"))
      (node (ref "U2") (pin "3") (pinfunction "V+_3") (pintype "power_in"))
    )
    (net (code "39") (name "Net-(U2-V-)") (class "Default")
      (node (ref "C10") (pin "1") (pinfunction "1_1") (pintype "passive"))
      (node (ref "U2") (pin "7") (pinfunction "V-_7") (pintype "power_in"))
    )
    (net (code "40") (name "Net-(U2-~{FORCEOFF})") (class "Default")
      (node (ref "R14") (pin "1") (pinfunction "1_1") (pintype "passive"))
      (node (ref "U2") (pin "16") (pinfunction "~{FORCEOFF}_16") (pintype "input"))
    )
    (net (code "41") (name "Net-(U2-~{INVALID})") (class "Default")
      (node (ref "TP31") (pin "1") (pinfunction "1_1") (pintype "passive"))
      (node (ref "U2") (pin "10") (pinfunction "~{INVALID}_10") (pintype "output"))
    )
    (net (code "42") (name "Net-(U3-TRIM)") (class "Default")
      (node (ref "R5") (pin "2") (pinfunction "2_2") (pintype "passive"))
      (node (ref "U3") (pin "4") (pinfunction "TRIM_4") (pintype "input"))
    )
    (net (code "43") (name "Net-(U3-~{EN})") (class "Default")
      (node (ref "R10") (pin "2") (pinfunction "2_2") (pintype "passive"))
      (node (ref "TP30") (pin "1") (pinfunction "1_1") (pintype "passive"))
      (node (ref "U3") (pin "1") (pinfunction "~{EN}_1") (pintype "input"))
    )
    (net (code "44") (name "Net-(U7-PA6)") (class "Default")
      (node (ref "TP22") (pin "1") (pinfunction "1_1") (pintype "passive"))
      (node (ref "U7") (pin "16") (pinfunction "PA6_16") (pintype "bidirectional"))
    )
    (net (code "45") (name "Net-(U7-PF0-OSC_IN)") (class "Default")
      (node (ref "C28") (pin "1") (pinfunction "1_1") (pintype "passive"))
      (node (ref "U7") (pin "5") (pinfunction "PF0-OSC_IN_5") (pintype "bidirectional"))
      (node (ref "X1") (pin "1") (pinfunction "1_1") (pintype "passive"))
    )
    (net (code "46") (name "Net-(U7-PF1-OSC_OUT)") (class "Default")
      (node (ref "C27") (pin "1") (pinfunction "1_1") (pintype "passive"))
      (node (ref "U7") (pin "6") (pinfunction "PF1-OSC_OUT_6") (pintype "bidirectional"))
      (node (ref "X1") (pin "3") (pinfunction "2_3") (pintype "passive"))
    )
    (net (code "47") (name "Net-(U10-FB)") (class "Default")
      (node (ref "C22") (pin "1") (pinfunction "1_1") (pintype "passive"))
      (node (ref "R1") (pin "1") (pinfunction "1_1") (pintype "passive"))
      (node (ref "R2") (pin "2") (pinfunction "2_2") (pintype "passive"))
      (node (ref "TP27") (pin "1") (pinfunction "1_1") (pintype "passive"))
      (node (ref "U10") (pin "8") (pinfunction "FB_8") (pintype "passive"))
    )
    (net (code "48") (name "Net-(U10-L1)") (class "Default")
      (node (ref "L1") (pin "1") (pinfunction "1_1") (pintype "passive"))
      (node (ref "U10") (pin "1") (pinfunction "L1_1") (pintype "passive"))
    )
    (net (code "49") (name "Net-(U10-L2)") (class "Default")
      (node (ref "L1") (pin "2") (pinfunction "2_2") (pintype "passive"))
      (node (ref "U10") (pin "10") (pinfunction "L2_10") (pintype "passive"))
    )
    (net (code "50") (name "Net-(U10-PG)") (class "Default")
      (node (ref "R9") (pin "1") (pinfunction "1_1") (pintype "passive"))
      (node (ref "TP26") (pin "1") (pinfunction "1_1") (pintype "passive"))
      (node (ref "U10") (pin "5") (pinfunction "PG_5") (pintype "open_collector"))
    )
    (net (code "51") (name "Net-(U10-PS{slash}SYNC)") (class "Default")
      (node (ref "R11") (pin "2") (pinfunction "2_2") (pintype "passive"))
      (node (ref "R13") (pin "1") (pinfunction "1_1") (pintype "passive"))
      (node (ref "TP29") (pin "1") (pinfunction "1_1") (pintype "passive"))
      (node (ref "U10") (pin "4") (pinfunction "PS/SYNC_4") (pintype "input"))
    )
    (net (code "52") (name "Net-(U10-VAUX)") (class "Default")
      (node (ref "C7") (pin "1") (pinfunction "1_1") (pintype "passive"))
      (node (ref "TP28") (pin "1") (pinfunction "1_1") (pintype "passive"))
      (node (ref "U10") (pin "6") (pinfunction "VAUX_6") (pintype "output"))
    )
    (net (code "53") (name "Net-(U10-VIN)") (class "Default")
      (node (ref "C12") (pin "1") (pinfunction "1_1") (pintype "passive"))
      (node (ref "C20") (pin "1") (pinfunction "1_1") (pintype "passive"))
      (node (ref "R13") (pin "2") (pinfunction "2_2") (pintype "passive"))
      (node (ref "R18") (pin "1") (pinfunction "1_1") (pintype "passive"))
      (node (ref "R6") (pin "2") (pinfunction "2_2") (pintype "passive"))
      (node (ref "U10") (pin "2") (pinfunction "VIN_2") (pintype "power_in"))
    )
    (net (code "54") (name "PA0") (class "Default")
      (node (ref "R23") (pin "2") (pinfunction "2_2") (pintype "passive"))
      (node (ref "U7") (pin "10") (pinfunction "PA0_10") (pintype "bidirectional"))
    )
    (net (code "55") (name "PA2{slash}USART2_TX") (class "Default")
      (node (ref "J2") (pin "13") (pinfunction "CARD-TX_13") (pintype "passive"))
      (node (ref "U2") (pin "11") (pinfunction "T1IN_11") (pintype "input"))
      (node (ref "U7") (pin "12") (pinfunction "PA2_12") (pintype "bidirectional"))
    )
    (net (code "56") (name "PA3{slash}USART2_RX") (class "Default")
      (node (ref "J2") (pin "12") (pinfunction "CARD-RX_12") (pintype "passive"))
      (node (ref "R12") (pin "2") (pinfunction "2_2") (pintype "passive"))
      (node (ref "U7") (pin "13") (pinfunction "PA3_13") (pintype "bidirectional"))
    )
    (net (code "57") (name "PA4{slash}DAC0") (class "Default")
      (node (ref "R8") (pin "1") (pinfunction "1_1") (pintype "passive"))
      (node (ref "TP25") (pin "1") (pinfunction "1_1") (pintype "passive"))
      (node (ref "U7") (pin "14") (pinfunction "PA4_14") (pintype "bidirectional"))
    )
    (net (code "58") (name "PA5{slash}DAC1") (class "Default")
      (node (ref "R7") (pin "1") (pinfunction "1_1") (pintype "passive"))
      (node (ref "TP15") (pin "1") (pinfunction "1_1") (pintype "passive"))
      (node (ref "U7") (pin "15") (pinfunction "PA5_15") (pintype "bidirectional"))
    )
    (net (code "59") (name "SWCLK") (class "Default")
      (node (ref "J2") (pin "15") (pinfunction "SWCLK_15") (pintype "passive"))
      (node (ref "U7") (pin "37") (pinfunction "PA14-SWCLK_37") (pintype "bidirectional"))
    )
    (net (code "60") (name "SWDIO") (class "Default")
      (node (ref "J2") (pin "14") (pinfunction "SWDIO_14") (pintype "passive"))
      (node (ref "U7") (pin "34") (pinfunction "PA13-SWDIO_34") (pintype "bidirectional"))
    )
    (net (code "61") (name "TPS-VOUT-3.3V") (class "Default")
      (node (ref "C13") (pin "1") (pinfunction "1_1") (pintype "passive"))
      (node (ref "C15") (pin "1") (pinfunction "1_1") (pintype "passive"))
      (node (ref "C19") (pin "1") (pinfunction "1_1") (pintype "passive"))
      (node (ref "C23") (pin "1") (pinfunction "1_1") (pintype "passive"))
      (node (ref "R1") (pin "2") (pinfunction "2_2") (pintype "passive"))
      (node (ref "R20") (pin "2") (pinfunction "2_2") (pintype "passive"))
      (node (ref "R9") (pin "2") (pinfunction "2_2") (pintype "passive"))
      (node (ref "TP6") (pin "1") (pinfunction "1_1") (pintype "passive"))
      (node (ref "U10") (pin "9") (pinfunction "VOUT_9") (pintype "power_in"))
    )
    (net (code "62") (name "VBUS") (class "Default")
      (node (ref "C5") (pin "1") (pinfunction "1_1") (pintype "passive"))
      (node (ref "C6") (pin "1") (pinfunction "1_1") (pintype "passive"))
      (node (ref "CF1") (pin "5") (pinfunction "VBUS_5") (pintype "passive"))
      (node (ref "CF1") (pin "6") (pinfunction "VBUS_6") (pintype "passive"))
      (node (ref "R6") (pin "1") (pinfunction "1_1") (pintype "passive"))
      (node (ref "TP3") (pin "1") (pinfunction "1_1") (pintype "passive"))
      (node (ref "U3") (pin "5") (pinfunction "VOUT_5") (pintype "power_in"))
    )
    (net (code "63") (name "unconnected-(J2-DEVICE-D+-Pad4)") (class "Default")
      (node (ref "J2") (pin "4") (pinfunction "DEVICE-D+_4") (pintype "passive"))
    )
    (net (code "64") (name "unconnected-(J2-DEVICE-D--Pad5)") (class "Default")
      (node (ref "J2") (pin "5") (pinfunction "DEVICE-D-_5") (pintype "passive"))
    )
    (net (code "65") (name "unconnected-(J2-HOST-D+-Pad7)") (class "Default")
      (node (ref "J2") (pin "7") (pinfunction "HOST-D+_7") (pintype "passive"))
    )
    (net (code "66") (name "unconnected-(J2-HOST-D--Pad8)") (class "Default")
      (node (ref "J2") (pin "8") (pinfunction "HOST-D-_8") (pintype "passive"))
    )
    (net (code "67") (name "unconnected-(U7-PA1-Pad11)") (class "Default")
      (node (ref "U7") (pin "11") (pinfunction "PA1_11") (pintype "bidirectional"))
    )
    (net (code "68") (name "unconnected-(U7-PA7-Pad17)") (class "Default")
      (node (ref "U7") (pin "17") (pinfunction "PA7_17") (pintype "bidirectional"))
    )
    (net (code "69") (name "unconnected-(U7-PA8-Pad29)") (class "Default")
      (node (ref "U7") (pin "29") (pinfunction "PA8_29") (pintype "bidirectional"))
    )
    (net (code "70") (name "unconnected-(U7-PA15-Pad38)") (class "Default")
      (node (ref "U7") (pin "38") (pinfunction "PA15_38") (pintype "bidirectional"))
    )
    (net (code "71") (name "unconnected-(U7-PB0-Pad18)") (class "Default")
      (node (ref "U7") (pin "18") (pinfunction "PB0_18") (pintype "bidirectional"))
    )
    (net (code "72") (name "unconnected-(U7-PB1-Pad19)") (class "Default")
      (node (ref "U7") (pin "19") (pinfunction "PB1_19") (pintype "bidirectional"))
    )
    (net (code "73") (name "unconnected-(U7-PB2-Pad20)") (class "Default")
      (node (ref "U7") (pin "20") (pinfunction "PB2_20") (pintype "bidirectional"))
    )
    (net (code "74") (name "unconnected-(U7-PB3-Pad39)") (class "Default")
      (node (ref "U7") (pin "39") (pinfunction "PB3_39") (pintype "bidirectional"))
    )
    (net (code "75") (name "unconnected-(U7-PB4-Pad40)") (class "Default")
      (node (ref "U7") (pin "40") (pinfunction "PB4_40") (pintype "bidirectional"))
    )
    (net (code "76") (name "unconnected-(U7-PB5-Pad41)") (class "Default")
      (node (ref "U7") (pin "41") (pinfunction "PB5_41") (pintype "bidirectional"))
    )
    (net (code "77") (name "unconnected-(U7-PB6-Pad42)") (class "Default")
      (node (ref "U7") (pin "42") (pinfunction "PB6_42") (pintype "bidirectional"))
    )
    (net (code "78") (name "unconnected-(U7-PB7-Pad43)") (class "Default")
      (node (ref "U7") (pin "43") (pinfunction "PB7_43") (pintype "bidirectional"))
    )
    (net (code "79") (name "unconnected-(U7-PB8-Pad45)") (class "Default")
      (node (ref "U7") (pin "45") (pinfunction "PB8_45") (pintype "bidirectional"))
    )
    (net (code "80") (name "unconnected-(U7-PB9-Pad46)") (class "Default")
      (node (ref "U7") (pin "46") (pinfunction "PB9_46") (pintype "bidirectional"))
    )
    (net (code "81") (name "unconnected-(U7-PB10-Pad21)") (class "Default")
      (node (ref "U7") (pin "21") (pinfunction "PB10_21") (pintype "bidirectional"))
    )
    (net (code "82") (name "unconnected-(U7-PB11-Pad22)") (class "Default")
      (node (ref "U7") (pin "22") (pinfunction "PB11_22") (pintype "bidirectional"))
    )
    (net (code "83") (name "unconnected-(U7-PB12-Pad25)") (class "Default")
      (node (ref "U7") (pin "25") (pinfunction "PB12_25") (pintype "bidirectional"))
    )
    (net (code "84") (name "unconnected-(U7-PB13-Pad26)") (class "Default")
      (node (ref "U7") (pin "26") (pinfunction "PB13_26") (pintype "bidirectional"))
    )
    (net (code "85") (name "unconnected-(U7-PB14-Pad27)") (class "Default")
      (node (ref "U7") (pin "27") (pinfunction "PB14_27") (pintype "bidirectional"))
    )
    (net (code "86") (name "unconnected-(U7-PB15-Pad28)") (class "Default")
      (node (ref "U7") (pin "28") (pinfunction "PB15_28") (pintype "bidirectional"))
    )
    (net (code "87") (name "unconnected-(U7-PC13-Pad2)") (class "Default")
      (node (ref "U7") (pin "2") (pinfunction "PC13_2") (pintype "bidirectional"))
    )
    (net (code "88") (name "unconnected-(U7-PC14-OSC32_IN-Pad3)") (class "Default")
      (node (ref "U7") (pin "3") (pinfunction "PC14-OSC32_IN_3") (pintype "bidirectional"))
    )
    (net (code "89") (name "unconnected-(U7-PC15-OSC32_OUT-Pad4)") (class "Default")
      (node (ref "U7") (pin "4") (pinfunction "PC15-OSC32_OUT_4") (pintype "bidirectional"))
    )
    (net (code "90") (name "~{SHDN-3.3V}") (class "Default")
      (node (ref "D7") (pin "A") (pinfunction "A_A") (pintype "passive"))
      (node (ref "R18") (pin "2") (pinfunction "2_2") (pintype "passive"))
      (node (ref "TP9") (pin "1") (pinfunction "1_1") (pintype "passive"))
      (node (ref "U10") (pin "3") (pinfunction "EN_3") (pintype "input"))
    )
    (net (code "91") (name "~{SHUTDOWN}") (class "Default")
      (node (ref "CF1") (pin "1") (pinfunction "~{SD}_1") (pintype "passive"))
      (node (ref "CF1") (pin "2") (pinfunction "~{SD}_2") (pintype "passive"))
      (node (ref "D7") (pin "C") (pinfunction "C_C") (pintype "passive"))
      (node (ref "J1") (pin "2A") (pinfunction "2A_2A") (pintype "passive"))
      (node (ref "J1") (pin "2B") (pinfunction "2B_2B") (pintype "passive"))
      (node (ref "J1") (pin "4A") (pinfunction "4A_4A") (pintype "passive"))
      (node (ref "J1") (pin "4B") (pinfunction "4B_4B") (pintype "passive"))
      (node (ref "TP11") (pin "1") (pinfunction "1_1") (pintype "passive"))
    )
  )
)
